# macu_board.net
KiCad netlist of a schematic drawn in EAGLE
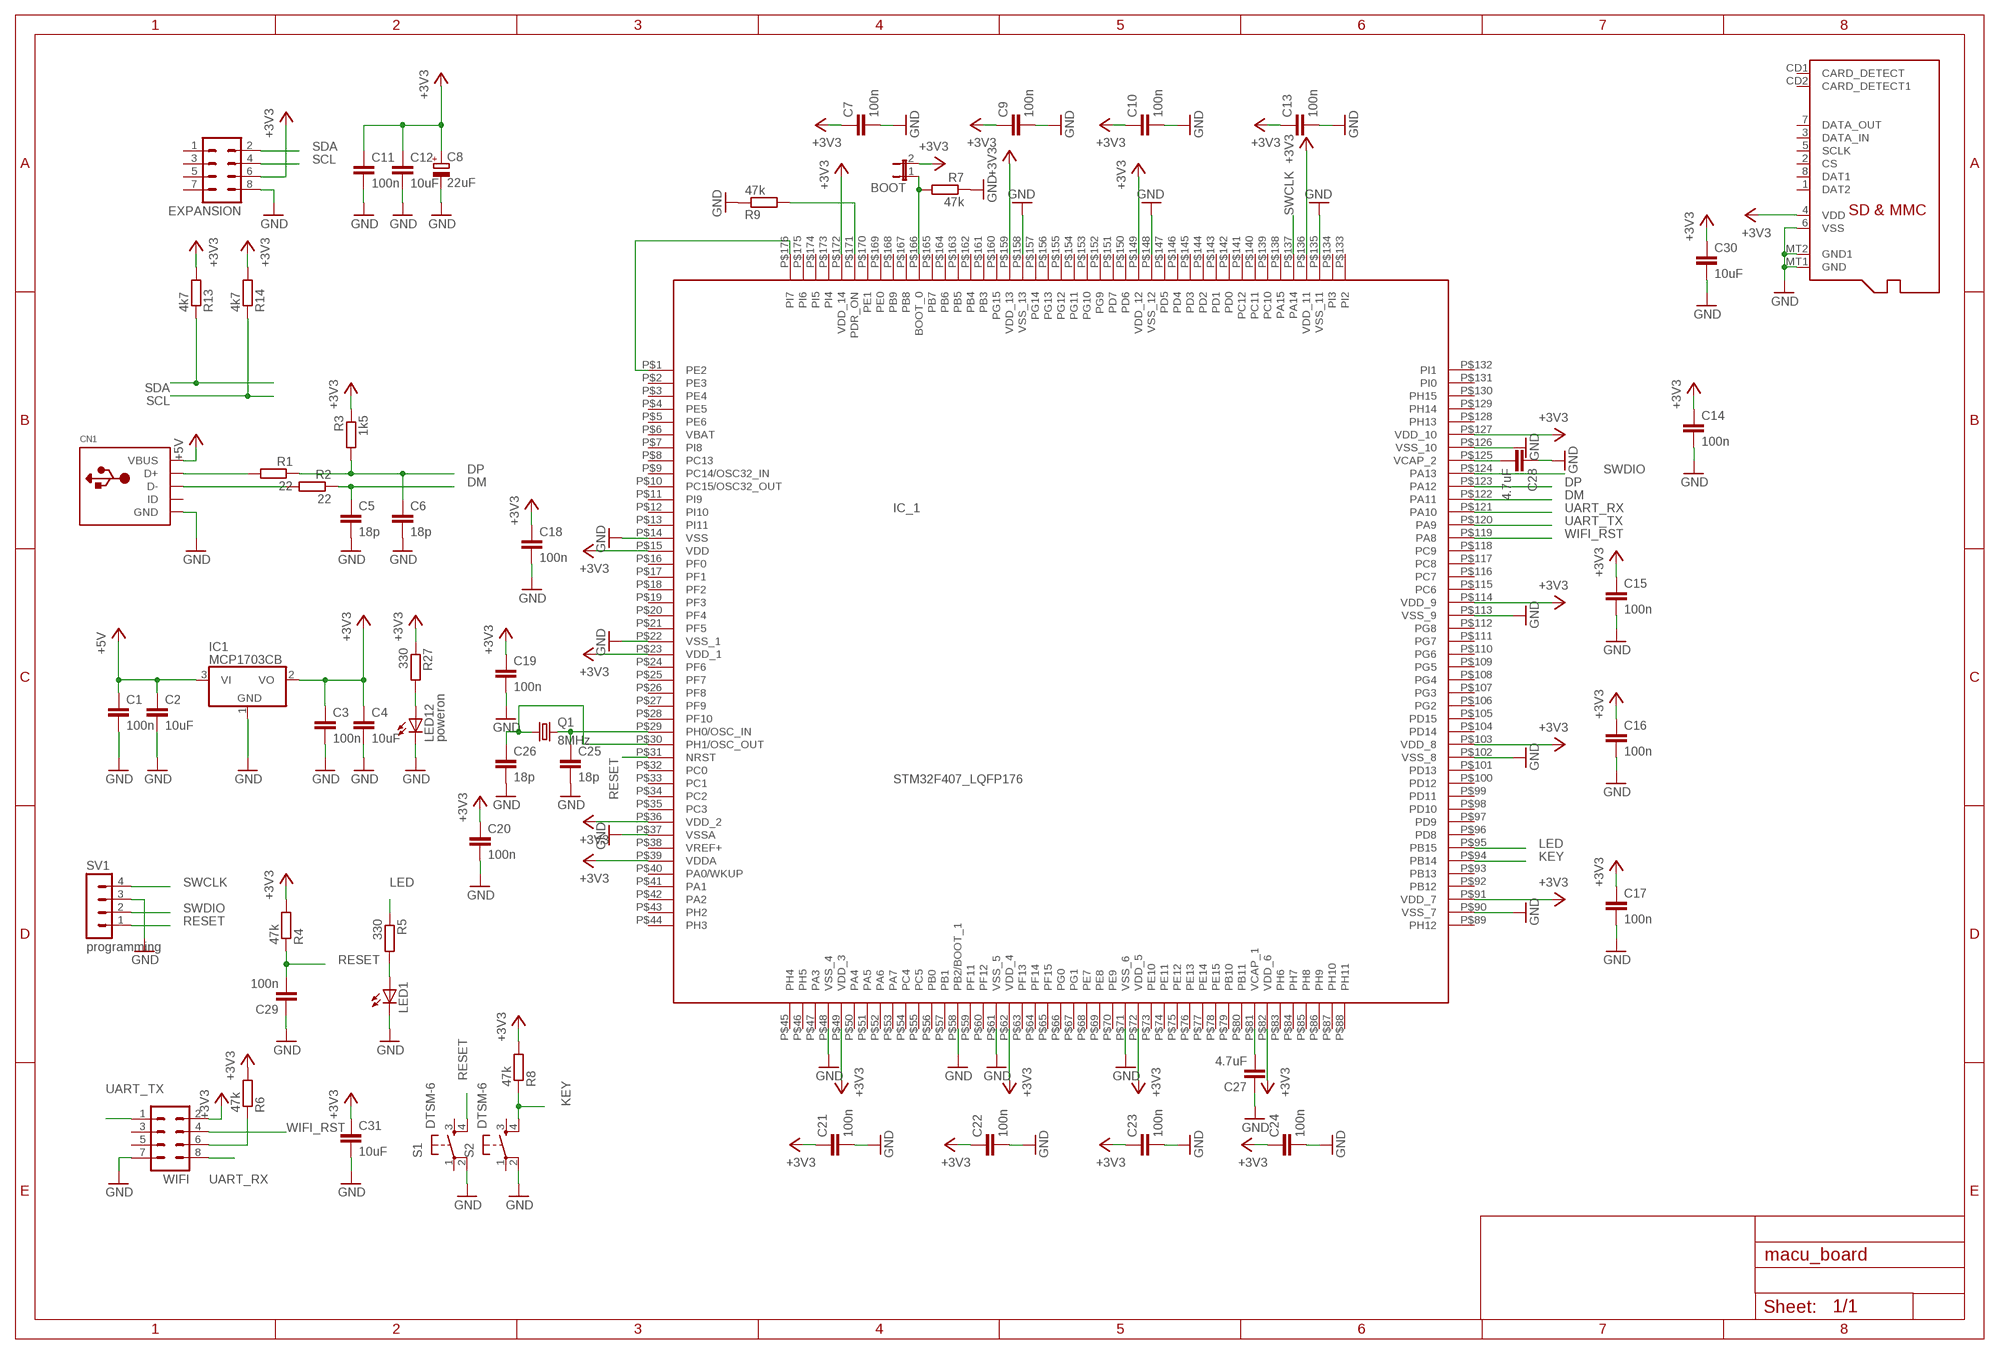
[diagram p0: schematic, sheet 1]

(export (version "E")
  (design (tool "Eeschema 10.0.6"))
  (components
    (comp (ref "BOOT")
      (value "JP1E")
      (footprint "eagle-import:JP1")
      (libsource (lib "eagle-import") (part "JP1E"))
    )
    (comp (ref "C1")
      (value "100n")
      (footprint "eagle-import:C0805")
      (libsource (lib "eagle-import") (part "C-EUC0805"))
    )
    (comp (ref "C2")
      (value "10uF")
      (footprint "eagle-import:C0805")
      (libsource (lib "eagle-import") (part "C-EUC0805"))
    )
    (comp (ref "C3")
      (value "100n")
      (footprint "eagle-import:C0805")
      (libsource (lib "eagle-import") (part "C-EUC0805"))
    )
    (comp (ref "C4")
      (value "10uF")
      (footprint "eagle-import:C0805")
      (libsource (lib "eagle-import") (part "C-EUC0805"))
    )
    (comp (ref "C5")
      (value "18p")
      (footprint "eagle-import:C0805")
      (libsource (lib "eagle-import") (part "C-EUC0805"))
    )
    (comp (ref "C6")
      (value "18p")
      (footprint "eagle-import:C0805")
      (libsource (lib "eagle-import") (part "C-EUC0805"))
    )
    (comp (ref "C7")
      (value "100n")
      (footprint "eagle-import:C0805")
      (libsource (lib "eagle-import") (part "C-EUC0805"))
    )
    (comp (ref "C8")
      (value "22uF")
      (footprint "eagle-import:153CLV-0505")
      (libsource (lib "eagle-import") (part "CPOL-EU153CLV-0505"))
    )
    (comp (ref "C9")
      (value "100n")
      (footprint "eagle-import:C0805")
      (libsource (lib "eagle-import") (part "C-EUC0805"))
    )
    (comp (ref "C10")
      (value "100n")
      (footprint "eagle-import:C0805")
      (libsource (lib "eagle-import") (part "C-EUC0805"))
    )
    (comp (ref "C11")
      (value "100n")
      (footprint "eagle-import:C0805")
      (libsource (lib "eagle-import") (part "C-EUC0805"))
    )
    (comp (ref "C12")
      (value "10uF")
      (footprint "eagle-import:C0805")
      (libsource (lib "eagle-import") (part "C-EUC0805"))
    )
    (comp (ref "C13")
      (value "100n")
      (footprint "eagle-import:C0805")
      (libsource (lib "eagle-import") (part "C-EUC0805"))
    )
    (comp (ref "C14")
      (value "100n")
      (footprint "eagle-import:C0805")
      (libsource (lib "eagle-import") (part "C-EUC0805"))
    )
    (comp (ref "C15")
      (value "100n")
      (footprint "eagle-import:C0805")
      (libsource (lib "eagle-import") (part "C-EUC0805"))
    )
    (comp (ref "C16")
      (value "100n")
      (footprint "eagle-import:C0805")
      (libsource (lib "eagle-import") (part "C-EUC0805"))
    )
    (comp (ref "C17")
      (value "100n")
      (footprint "eagle-import:C0805")
      (libsource (lib "eagle-import") (part "C-EUC0805"))
    )
    (comp (ref "C18")
      (value "100n")
      (footprint "eagle-import:C0805")
      (libsource (lib "eagle-import") (part "C-EUC0805"))
    )
    (comp (ref "C19")
      (value "100n")
      (footprint "eagle-import:C0805")
      (libsource (lib "eagle-import") (part "C-EUC0805"))
    )
    (comp (ref "C20")
      (value "100n")
      (footprint "eagle-import:C0805")
      (libsource (lib "eagle-import") (part "C-EUC0805"))
    )
    (comp (ref "C21")
      (value "100n")
      (footprint "eagle-import:C0805")
      (libsource (lib "eagle-import") (part "C-EUC0805"))
    )
    (comp (ref "C22")
      (value "100n")
      (footprint "eagle-import:C0805")
      (libsource (lib "eagle-import") (part "C-EUC0805"))
    )
    (comp (ref "C23")
      (value "100n")
      (footprint "eagle-import:C0805")
      (libsource (lib "eagle-import") (part "C-EUC0805"))
    )
    (comp (ref "C24")
      (value "100n")
      (footprint "eagle-import:C0805")
      (libsource (lib "eagle-import") (part "C-EUC0805"))
    )
    (comp (ref "C25")
      (value "18p")
      (footprint "eagle-import:C0805")
      (libsource (lib "eagle-import") (part "C-EUC0805"))
    )
    (comp (ref "C26")
      (value "18p")
      (footprint "eagle-import:C0805")
      (libsource (lib "eagle-import") (part "C-EUC0805"))
    )
    (comp (ref "C27")
      (value "4.7uF")
      (footprint "eagle-import:C0805")
      (libsource (lib "eagle-import") (part "C-EUC0805"))
    )
    (comp (ref "C28")
      (value "4.7uF")
      (footprint "eagle-import:C0805")
      (libsource (lib "eagle-import") (part "C-EUC0805"))
    )
    (comp (ref "C29")
      (value "100n")
      (footprint "eagle-import:C0805")
      (libsource (lib "eagle-import") (part "C-EUC0805"))
    )
    (comp (ref "C30")
      (value "10uF")
      (footprint "eagle-import:C0805")
      (libsource (lib "eagle-import") (part "C-EUC0805"))
    )
    (comp (ref "C31")
      (value "10uF")
      (footprint "eagle-import:C0805")
      (libsource (lib "eagle-import") (part "C-EUC0805"))
    )
    (comp (ref "CN1")
      (value "USBMINIB")
      (footprint "eagle-import:USB-MINIB")
      (libsource (lib "eagle-import") (part "USBMINIB"))
    )
    (comp (ref "EXPANSION")
      (value "MA04-2")
      (footprint "eagle-import:MA04-2")
      (libsource (lib "eagle-import") (part "MA04-2"))
    )
    (comp (ref "IC1")
      (value "MCP1703CB")
      (footprint "eagle-import:SOT23")
      (libsource (lib "eagle-import") (part "MCP1703CB"))
    )
    (comp (ref "IC_1")
      (value "STM32F407_LQFP176")
      (footprint "eagle-import:STM32F407_LQFP176")
      (libsource (lib "eagle-import") (part "STM32F407_LQFP176"))
    )
    (comp (ref "LED1")
      (value "LEDCHIPLED_1206")
      (footprint "eagle-import:CHIPLED_1206")
      (libsource (lib "eagle-import") (part "LEDCHIPLED_1206"))
    )
    (comp (ref "LED12")
      (value "poweron")
      (footprint "eagle-import:CHIPLED_1206")
      (libsource (lib "eagle-import") (part "LEDCHIPLED_1206"))
    )
    (comp (ref "Q1")
      (value "8MHz")
      (footprint "eagle-import:CTS406")
      (libsource (lib "eagle-import") (part "CRYSTALCTS406"))
    )
    (comp (ref "R1")
      (value "22")
      (footprint "eagle-import:M0805")
      (libsource (lib "eagle-import") (part "R-EU_M0805"))
    )
    (comp (ref "R2")
      (value "22")
      (footprint "eagle-import:M0805")
      (libsource (lib "eagle-import") (part "R-EU_M0805"))
    )
    (comp (ref "R3")
      (value "1k5")
      (footprint "eagle-import:M0805")
      (libsource (lib "eagle-import") (part "R-EU_M0805"))
    )
    (comp (ref "R4")
      (value "47k")
      (footprint "eagle-import:M0805")
      (libsource (lib "eagle-import") (part "R-EU_M0805"))
    )
    (comp (ref "R5")
      (value "330")
      (footprint "eagle-import:M0805")
      (libsource (lib "eagle-import") (part "R-EU_M0805"))
    )
    (comp (ref "R6")
      (value "47k")
      (footprint "eagle-import:M0805")
      (libsource (lib "eagle-import") (part "R-EU_M0805"))
    )
    (comp (ref "R7")
      (value "47k")
      (footprint "eagle-import:M0805")
      (libsource (lib "eagle-import") (part "R-EU_M0805"))
    )
    (comp (ref "R8")
      (value "47k")
      (footprint "eagle-import:M0805")
      (libsource (lib "eagle-import") (part "R-EU_M0805"))
    )
    (comp (ref "R9")
      (value "47k")
      (footprint "eagle-import:M0805")
      (libsource (lib "eagle-import") (part "R-EU_M0805"))
    )
    (comp (ref "R13")
      (value "4k7")
      (footprint "eagle-import:M0805")
      (libsource (lib "eagle-import") (part "R-EU_M0805"))
    )
    (comp (ref "R14")
      (value "4k7")
      (footprint "eagle-import:M0805")
      (libsource (lib "eagle-import") (part "R-EU_M0805"))
    )
    (comp (ref "R27")
      (value "330")
      (footprint "eagle-import:M0805")
      (libsource (lib "eagle-import") (part "R-EU_M0805"))
    )
    (comp (ref "S1")
      (value "DTSM-6")
      (footprint "eagle-import:DTSM-6")
      (libsource (lib "eagle-import") (part "DTSM-6"))
    )
    (comp (ref "S2")
      (value "DTSM-6")
      (footprint "eagle-import:DTSM-6")
      (libsource (lib "eagle-import") (part "DTSM-6"))
    )
    (comp (ref "SV1")
      (value "programming")
      (footprint "eagle-import:MA04-1")
      (libsource (lib "eagle-import") (part "MA04-1"))
    )
    (comp (ref "U$1")
      (value "MICROSD")
      (footprint "eagle-import:MICROSD")
      (libsource (lib "eagle-import") (part "MICROSD"))
    )
    (comp (ref "WIFI")
      (value "MA04-2")
      (footprint "eagle-import:MA04-2")
      (libsource (lib "eagle-import") (part "MA04-2"))
    )
  )
  (nets
    (net (code "1") (name "+3V3") (class "Default")
      (node (ref "BOOT") (pin "2") (pinfunction "2_2") (pintype "passive"))
      (node (ref "C10") (pin "1") (pinfunction "1_1") (pintype "passive"))
      (node (ref "C11") (pin "1") (pinfunction "1_1") (pintype "passive"))
      (node (ref "C12") (pin "1") (pinfunction "1_1") (pintype "passive"))
      (node (ref "C13") (pin "1") (pinfunction "1_1") (pintype "passive"))
      (node (ref "C14") (pin "1") (pinfunction "1_1") (pintype "passive"))
      (node (ref "C15") (pin "1") (pinfunction "1_1") (pintype "passive"))
      (node (ref "C16") (pin "1") (pinfunction "1_1") (pintype "passive"))
      (node (ref "C17") (pin "1") (pinfunction "1_1") (pintype "passive"))
      (node (ref "C18") (pin "1") (pinfunction "1_1") (pintype "passive"))
      (node (ref "C19") (pin "1") (pinfunction "1_1") (pintype "passive"))
      (node (ref "C20") (pin "1") (pinfunction "1_1") (pintype "passive"))
      (node (ref "C21") (pin "1") (pinfunction "1_1") (pintype "passive"))
      (node (ref "C22") (pin "1") (pinfunction "1_1") (pintype "passive"))
      (node (ref "C23") (pin "1") (pinfunction "1_1") (pintype "passive"))
      (node (ref "C24") (pin "1") (pinfunction "1_1") (pintype "passive"))
      (node (ref "C3") (pin "1") (pinfunction "1_1") (pintype "passive"))
      (node (ref "C30") (pin "1") (pinfunction "1_1") (pintype "passive"))
      (node (ref "C31") (pin "1") (pinfunction "1_1") (pintype "passive"))
      (node (ref "C4") (pin "1") (pinfunction "1_1") (pintype "passive"))
      (node (ref "C7") (pin "1") (pinfunction "1_1") (pintype "passive"))
      (node (ref "C8") (pin "+") (pinfunction "+_+") (pintype "passive"))
      (node (ref "C9") (pin "1") (pinfunction "1_1") (pintype "passive"))
      (node (ref "EXPANSION") (pin "6") (pinfunction "6_6") (pintype "passive"))
      (node (ref "IC1") (pin "2") (pinfunction "VO_2") (pintype "passive"))
      (node (ref "IC_1") (pin "P$103") (pinfunction "VDD_8_P$103") (pintype "power_in"))
      (node (ref "IC_1") (pin "P$114") (pinfunction "VDD_9_P$114") (pintype "power_in"))
      (node (ref "IC_1") (pin "P$127") (pinfunction "VDD_10_P$127") (pintype "power_in"))
      (node (ref "IC_1") (pin "P$136") (pinfunction "VDD_11_P$136") (pintype "power_in"))
      (node (ref "IC_1") (pin "P$149") (pinfunction "VDD_12_P$149") (pintype "power_in"))
      (node (ref "IC_1") (pin "P$15") (pinfunction "VDD_P$15") (pintype "power_in"))
      (node (ref "IC_1") (pin "P$159") (pinfunction "VDD_13_P$159") (pintype "power_in"))
      (node (ref "IC_1") (pin "P$172") (pinfunction "VDD_14_P$172") (pintype "power_in"))
      (node (ref "IC_1") (pin "P$23") (pinfunction "VDD_1_P$23") (pintype "power_in"))
      (node (ref "IC_1") (pin "P$36") (pinfunction "VDD_2_P$36") (pintype "power_in"))
      (node (ref "IC_1") (pin "P$39") (pinfunction "VDDA_P$39") (pintype "power_in"))
      (node (ref "IC_1") (pin "P$49") (pinfunction "VDD_3_P$49") (pintype "power_in"))
      (node (ref "IC_1") (pin "P$62") (pinfunction "VDD_4_P$62") (pintype "power_in"))
      (node (ref "IC_1") (pin "P$72") (pinfunction "VDD_5_P$72") (pintype "power_in"))
      (node (ref "IC_1") (pin "P$82") (pinfunction "VDD_6_P$82") (pintype "power_in"))
      (node (ref "IC_1") (pin "P$91") (pinfunction "VDD_7_P$91") (pintype "power_in"))
      (node (ref "R13") (pin "2") (pinfunction "2_2") (pintype "passive"))
      (node (ref "R14") (pin "2") (pinfunction "2_2") (pintype "passive"))
      (node (ref "R27") (pin "1") (pinfunction "1_1") (pintype "passive"))
      (node (ref "R3") (pin "1") (pinfunction "1_1") (pintype "passive"))
      (node (ref "R4") (pin "2") (pinfunction "2_2") (pintype "passive"))
      (node (ref "R6") (pin "2") (pinfunction "2_2") (pintype "passive"))
      (node (ref "R8") (pin "2") (pinfunction "2_2") (pintype "passive"))
      (node (ref "U$1") (pin "4") (pinfunction "VDD_4") (pintype "power_in"))
      (node (ref "WIFI") (pin "2") (pinfunction "2_2") (pintype "passive"))
    )
    (net (code "2") (name "+5V") (class "Default")
      (node (ref "C1") (pin "1") (pinfunction "1_1") (pintype "passive"))
      (node (ref "C2") (pin "1") (pinfunction "1_1") (pintype "passive"))
      (node (ref "CN1") (pin "VBUS") (pinfunction "VBUS_VBUS") (pintype "power_in"))
      (node (ref "IC1") (pin "3") (pinfunction "VI_3") (pintype "input"))
    )
    (net (code "3") (name "/DM") (class "Default")
      (node (ref "C5") (pin "1") (pinfunction "1_1") (pintype "passive"))
      (node (ref "IC_1") (pin "P$122") (pinfunction "PA11_P$122") (pintype "bidirectional"))
      (node (ref "R2") (pin "1") (pinfunction "1_1") (pintype "passive"))
    )
    (net (code "4") (name "/DP") (class "Default")
      (node (ref "C6") (pin "1") (pinfunction "1_1") (pintype "passive"))
      (node (ref "IC_1") (pin "P$123") (pinfunction "PA12_P$123") (pintype "bidirectional"))
      (node (ref "R1") (pin "1") (pinfunction "1_1") (pintype "passive"))
      (node (ref "R3") (pin "2") (pinfunction "2_2") (pintype "passive"))
    )
    (net (code "5") (name "/KEY") (class "Default")
      (node (ref "IC_1") (pin "P$94") (pinfunction "PB14_P$94") (pintype "bidirectional"))
      (node (ref "R8") (pin "1") (pinfunction "1_1") (pintype "passive"))
      (node (ref "S2") (pin "4") (pinfunction "4_4") (pintype "passive"))
    )
    (net (code "6") (name "/LED") (class "Default")
      (node (ref "IC_1") (pin "P$95") (pinfunction "PB15_P$95") (pintype "bidirectional"))
      (node (ref "R5") (pin "1") (pinfunction "1_1") (pintype "passive"))
    )
    (net (code "7") (name "/RESET") (class "Default")
      (node (ref "C29") (pin "2") (pinfunction "2_2") (pintype "passive"))
      (node (ref "IC_1") (pin "P$31") (pinfunction "NRST_P$31") (pintype "bidirectional"))
      (node (ref "R4") (pin "1") (pinfunction "1_1") (pintype "passive"))
      (node (ref "S1") (pin "4") (pinfunction "4_4") (pintype "passive"))
      (node (ref "SV1") (pin "1") (pinfunction "1_1") (pintype "passive"))
    )
    (net (code "8") (name "/SCL") (class "Default")
      (node (ref "EXPANSION") (pin "4") (pinfunction "4_4") (pintype "passive"))
      (node (ref "R14") (pin "1") (pinfunction "1_1") (pintype "passive"))
    )
    (net (code "9") (name "/SDA") (class "Default")
      (node (ref "EXPANSION") (pin "2") (pinfunction "2_2") (pintype "passive"))
      (node (ref "R13") (pin "1") (pinfunction "1_1") (pintype "passive"))
    )
    (net (code "10") (name "/SWCLK") (class "Default")
      (node (ref "IC_1") (pin "P$137") (pinfunction "PA14_P$137") (pintype "bidirectional"))
      (node (ref "SV1") (pin "4") (pinfunction "4_4") (pintype "passive"))
    )
    (net (code "11") (name "/SWDIO") (class "Default")
      (node (ref "IC_1") (pin "P$124") (pinfunction "PA13_P$124") (pintype "bidirectional"))
      (node (ref "SV1") (pin "2") (pinfunction "2_2") (pintype "passive"))
    )
    (net (code "12") (name "/UART_RX") (class "Default")
      (node (ref "IC_1") (pin "P$121") (pinfunction "PA10_P$121") (pintype "bidirectional"))
      (node (ref "WIFI") (pin "8") (pinfunction "8_8") (pintype "passive"))
    )
    (net (code "13") (name "/UART_TX") (class "Default")
      (node (ref "IC_1") (pin "P$120") (pinfunction "PA9_P$120") (pintype "bidirectional"))
      (node (ref "WIFI") (pin "1") (pinfunction "1_1") (pintype "passive"))
    )
    (net (code "14") (name "/VBAT") (class "Default")
      (node (ref "IC_1") (pin "P$6") (pinfunction "VBAT_P$6") (pintype "power_in"))
    )
    (net (code "15") (name "/VREF+") (class "Default")
      (node (ref "IC_1") (pin "P$38") (pinfunction "VREF+_P$38") (pintype "power_in"))
    )
    (net (code "16") (name "/WIFI_RST") (class "Default")
      (node (ref "IC_1") (pin "P$119") (pinfunction "PA8_P$119") (pintype "bidirectional"))
      (node (ref "WIFI") (pin "4") (pinfunction "4_4") (pintype "passive"))
    )
    (net (code "17") (name "GND") (class "Default")
      (node (ref "C1") (pin "2") (pinfunction "2_2") (pintype "passive"))
      (node (ref "C10") (pin "2") (pinfunction "2_2") (pintype "passive"))
      (node (ref "C11") (pin "2") (pinfunction "2_2") (pintype "passive"))
      (node (ref "C12") (pin "2") (pinfunction "2_2") (pintype "passive"))
      (node (ref "C13") (pin "2") (pinfunction "2_2") (pintype "passive"))
      (node (ref "C14") (pin "2") (pinfunction "2_2") (pintype "passive"))
      (node (ref "C15") (pin "2") (pinfunction "2_2") (pintype "passive"))
      (node (ref "C16") (pin "2") (pinfunction "2_2") (pintype "passive"))
      (node (ref "C17") (pin "2") (pinfunction "2_2") (pintype "passive"))
      (node (ref "C18") (pin "2") (pinfunction "2_2") (pintype "passive"))
      (node (ref "C19") (pin "2") (pinfunction "2_2") (pintype "passive"))
      (node (ref "C2") (pin "2") (pinfunction "2_2") (pintype "passive"))
      (node (ref "C20") (pin "2") (pinfunction "2_2") (pintype "passive"))
      (node (ref "C21") (pin "2") (pinfunction "2_2") (pintype "passive"))
      (node (ref "C22") (pin "2") (pinfunction "2_2") (pintype "passive"))
      (node (ref "C23") (pin "2") (pinfunction "2_2") (pintype "passive"))
      (node (ref "C24") (pin "2") (pinfunction "2_2") (pintype "passive"))
      (node (ref "C25") (pin "2") (pinfunction "2_2") (pintype "passive"))
      (node (ref "C26") (pin "2") (pinfunction "2_2") (pintype "passive"))
      (node (ref "C27") (pin "1") (pinfunction "1_1") (pintype "passive"))
      (node (ref "C28") (pin "1") (pinfunction "1_1") (pintype "passive"))
      (node (ref "C29") (pin "1") (pinfunction "1_1") (pintype "passive"))
      (node (ref "C3") (pin "2") (pinfunction "2_2") (pintype "passive"))
      (node (ref "C30") (pin "2") (pinfunction "2_2") (pintype "passive"))
      (node (ref "C31") (pin "2") (pinfunction "2_2") (pintype "passive"))
      (node (ref "C4") (pin "2") (pinfunction "2_2") (pintype "passive"))
      (node (ref "C5") (pin "2") (pinfunction "2_2") (pintype "passive"))
      (node (ref "C6") (pin "2") (pinfunction "2_2") (pintype "passive"))
      (node (ref "C7") (pin "2") (pinfunction "2_2") (pintype "passive"))
      (node (ref "C8") (pin "-") (pinfunction "-_-") (pintype "passive"))
      (node (ref "C9") (pin "2") (pinfunction "2_2") (pintype "passive"))
      (node (ref "CN1") (pin "GND") (pinfunction "GND_GND") (pintype "power_in"))
      (node (ref "EXPANSION") (pin "8") (pinfunction "8_8") (pintype "passive"))
      (node (ref "IC1") (pin "1") (pinfunction "GND_1") (pintype "passive"))
      (node (ref "IC_1") (pin "P$102") (pinfunction "VSS_8_P$102") (pintype "power_in"))
      (node (ref "IC_1") (pin "P$113") (pinfunction "VSS_9_P$113") (pintype "power_in"))
      (node (ref "IC_1") (pin "P$126") (pinfunction "VSS_10_P$126") (pintype "power_in"))
      (node (ref "IC_1") (pin "P$135") (pinfunction "VSS_11_P$135") (pintype "power_in"))
      (node (ref "IC_1") (pin "P$14") (pinfunction "VSS_P$14") (pintype "power_in"))
      (node (ref "IC_1") (pin "P$148") (pinfunction "VSS_12_P$148") (pintype "power_in"))
      (node (ref "IC_1") (pin "P$158") (pinfunction "VSS_13_P$158") (pintype "power_in"))
      (node (ref "IC_1") (pin "P$22") (pinfunction "VSS_1_P$22") (pintype "power_in"))
      (node (ref "IC_1") (pin "P$37") (pinfunction "VSSA_P$37") (pintype "power_in"))
      (node (ref "IC_1") (pin "P$48") (pinfunction "VSS_4_P$48") (pintype "power_in"))
      (node (ref "IC_1") (pin "P$58") (pinfunction "PB2/BOOT_1_P$58") (pintype "bidirectional"))
      (node (ref "IC_1") (pin "P$61") (pinfunction "VSS_5_P$61") (pintype "power_in"))
      (node (ref "IC_1") (pin "P$71") (pinfunction "VSS_6_P$71") (pintype "power_in"))
      (node (ref "IC_1") (pin "P$90") (pinfunction "VSS_7_P$90") (pintype "power_in"))
      (node (ref "LED1") (pin "C") (pinfunction "C_C") (pintype "passive"))
      (node (ref "LED12") (pin "C") (pinfunction "C_C") (pintype "passive"))
      (node (ref "R7") (pin "1") (pinfunction "1_1") (pintype "passive"))
      (node (ref "R9") (pin "1") (pinfunction "1_1") (pintype "passive"))
      (node (ref "S1") (pin "2") (pinfunction "2_2") (pintype "passive"))
      (node (ref "S2") (pin "2") (pinfunction "2_2") (pintype "passive"))
      (node (ref "SV1") (pin "3") (pinfunction "3_3") (pintype "passive"))
      (node (ref "U$1") (pin "6") (pinfunction "VSS_6") (pintype "power_in"))
      (node (ref "U$1") (pin "MT1") (pinfunction "GND_MT1") (pintype "power_in"))
      (node (ref "U$1") (pin "MT2") (pinfunction "GND1_MT2") (pintype "power_in"))
      (node (ref "WIFI") (pin "7") (pinfunction "7_7") (pintype "passive"))
    )
    (net (code "18") (name "Net-(CN1-PadD+)") (class "Default")
      (node (ref "CN1") (pin "D+") (pinfunction "D+_D+") (pintype "bidirectional"))
      (node (ref "R1") (pin "2") (pinfunction "2_2") (pintype "passive"))
    )
    (net (code "19") (name "Net-(CN1-PadD-)") (class "Default")
      (node (ref "CN1") (pin "D-") (pinfunction "D-_D-") (pintype "bidirectional"))
      (node (ref "R2") (pin "2") (pinfunction "2_2") (pintype "passive"))
    )
    (net (code "20") (name "Net-(IC_1-BOOT_0)") (class "Default")
      (node (ref "BOOT") (pin "1") (pinfunction "1_1") (pintype "passive"))
      (node (ref "IC_1") (pin "P$166") (pinfunction "BOOT_0_P$166") (pintype "bidirectional"))
      (node (ref "R7") (pin "2") (pinfunction "2_2") (pintype "passive"))
    )
    (net (code "21") (name "Net-(IC_1-PDR_ON)") (class "Default")
      (node (ref "IC_1") (pin "P$171") (pinfunction "PDR_ON_P$171") (pintype "bidirectional"))
      (node (ref "R9") (pin "2") (pinfunction "2_2") (pintype "passive"))
    )
    (net (code "22") (name "Net-(IC_1-PE2)") (class "Default")
      (node (ref "IC_1") (pin "P$1") (pinfunction "PE2_P$1") (pintype "bidirectional"))
      (node (ref "IC_1") (pin "P$176") (pinfunction "PI7_P$176") (pintype "bidirectional"))
    )
    (net (code "23") (name "Net-(IC_1-PH0{slash}OSC_IN)") (class "Default")
      (node (ref "C25") (pin "1") (pinfunction "1_1") (pintype "passive"))
      (node (ref "IC_1") (pin "P$29") (pinfunction "PH0/OSC_IN_P$29") (pintype "bidirectional"))
      (node (ref "Q1") (pin "3") (pinfunction "2_3") (pintype "passive"))
    )
    (net (code "24") (name "Net-(IC_1-PH1{slash}OSC_OUT)") (class "Default")
      (node (ref "C26") (pin "1") (pinfunction "1_1") (pintype "passive"))
      (node (ref "IC_1") (pin "P$30") (pinfunction "PH1/OSC_OUT_P$30") (pintype "bidirectional"))
      (node (ref "Q1") (pin "1") (pinfunction "1_1") (pintype "passive"))
    )
    (net (code "25") (name "Net-(IC_1-VCAP_1)") (class "Default")
      (node (ref "C27") (pin "2") (pinfunction "2_2") (pintype "passive"))
      (node (ref "IC_1") (pin "P$81") (pinfunction "VCAP_1_P$81") (pintype "power_in"))
    )
    (net (code "26") (name "Net-(IC_1-VCAP_2)") (class "Default")
      (node (ref "C28") (pin "2") (pinfunction "2_2") (pintype "passive"))
      (node (ref "IC_1") (pin "P$125") (pinfunction "VCAP_2_P$125") (pintype "power_in"))
    )
    (net (code "27") (name "Net-(LED1-PadA)") (class "Default")
      (node (ref "LED1") (pin "A") (pinfunction "A_A") (pintype "passive"))
      (node (ref "R5") (pin "2") (pinfunction "2_2") (pintype "passive"))
    )
    (net (code "28") (name "Net-(LED12-PadA)") (class "Default")
      (node (ref "LED12") (pin "A") (pinfunction "A_A") (pintype "passive"))
      (node (ref "R27") (pin "2") (pinfunction "2_2") (pintype "passive"))
    )
    (net (code "29") (name "Net-(R6-Pad1)") (class "Default")
      (node (ref "R6") (pin "1") (pinfunction "1_1") (pintype "passive"))
      (node (ref "WIFI") (pin "6") (pinfunction "6_6") (pintype "passive"))
    )
    (net (code "30") (name "unconnected-(CN1-PadID)") (class "Default")
      (node (ref "CN1") (pin "ID") (pinfunction "ID_ID") (pintype "bidirectional"))
    )
    (net (code "31") (name "unconnected-(EXPANSION-Pad1)") (class "Default")
      (node (ref "EXPANSION") (pin "1") (pinfunction "1_1") (pintype "passive"))
    )
    (net (code "32") (name "unconnected-(EXPANSION-Pad3)") (class "Default")
      (node (ref "EXPANSION") (pin "3") (pinfunction "3_3") (pintype "passive"))
    )
    (net (code "33") (name "unconnected-(EXPANSION-Pad5)") (class "Default")
      (node (ref "EXPANSION") (pin "5") (pinfunction "5_5") (pintype "passive"))
    )
    (net (code "34") (name "unconnected-(EXPANSION-Pad7)") (class "Default")
      (node (ref "EXPANSION") (pin "7") (pinfunction "7_7") (pintype "passive"))
    )
    (net (code "35") (name "unconnected-(IC_1-PA0{slash}WKUP-PadP$40)") (class "Default")
      (node (ref "IC_1") (pin "P$40") (pinfunction "PA0/WKUP_P$40") (pintype "bidirectional"))
    )
    (net (code "36") (name "unconnected-(IC_1-PA1-PadP$41)") (class "Default")
      (node (ref "IC_1") (pin "P$41") (pinfunction "PA1_P$41") (pintype "bidirectional"))
    )
    (net (code "37") (name "unconnected-(IC_1-PA2-PadP$42)") (class "Default")
      (node (ref "IC_1") (pin "P$42") (pinfunction "PA2_P$42") (pintype "bidirectional"))
    )
    (net (code "38") (name "unconnected-(IC_1-PA3-PadP$47)") (class "Default")
      (node (ref "IC_1") (pin "P$47") (pinfunction "PA3_P$47") (pintype "bidirectional"))
    )
    (net (code "39") (name "unconnected-(IC_1-PA4-PadP$50)") (class "Default")
      (node (ref "IC_1") (pin "P$50") (pinfunction "PA4_P$50") (pintype "bidirectional"))
    )
    (net (code "40") (name "unconnected-(IC_1-PA5-PadP$51)") (class "Default")
      (node (ref "IC_1") (pin "P$51") (pinfunction "PA5_P$51") (pintype "bidirectional"))
    )
    (net (code "41") (name "unconnected-(IC_1-PA6-PadP$52)") (class "Default")
      (node (ref "IC_1") (pin "P$52") (pinfunction "PA6_P$52") (pintype "bidirectional"))
    )
    (net (code "42") (name "unconnected-(IC_1-PA7-PadP$53)") (class "Default")
      (node (ref "IC_1") (pin "P$53") (pinfunction "PA7_P$53") (pintype "bidirectional"))
    )
    (net (code "43") (name "unconnected-(IC_1-PA15-PadP$138)") (class "Default")
      (node (ref "IC_1") (pin "P$138") (pinfunction "PA15_P$138") (pintype "bidirectional"))
    )
    (net (code "44") (name "unconnected-(IC_1-PB0-PadP$56)") (class "Default")
      (node (ref "IC_1") (pin "P$56") (pinfunction "PB0_P$56") (pintype "bidirectional"))
    )
    (net (code "45") (name "unconnected-(IC_1-PB1-PadP$57)") (class "Default")
      (node (ref "IC_1") (pin "P$57") (pinfunction "PB1_P$57") (pintype "bidirectional"))
    )
    (net (code "46") (name "unconnected-(IC_1-PB3-PadP$161)") (class "Default")
      (node (ref "IC_1") (pin "P$161") (pinfunction "PB3_P$161") (pintype "bidirectional"))
    )
    (net (code "47") (name "unconnected-(IC_1-PB4-PadP$162)") (class "Default")
      (node (ref "IC_1") (pin "P$162") (pinfunction "PB4_P$162") (pintype "bidirectional"))
    )
    (net (code "48") (name "unconnected-(IC_1-PB5-PadP$163)") (class "Default")
      (node (ref "IC_1") (pin "P$163") (pinfunction "PB5_P$163") (pintype "bidirectional"))
    )
    (net (code "49") (name "unconnected-(IC_1-PB6-PadP$164)") (class "Default")
      (node (ref "IC_1") (pin "P$164") (pinfunction "PB6_P$164") (pintype "bidirectional"))
    )
    (net (code "50") (name "unconnected-(IC_1-PB7-PadP$165)") (class "Default")
      (node (ref "IC_1") (pin "P$165") (pinfunction "PB7_P$165") (pintype "bidirectional"))
    )
    (net (code "51") (name "unconnected-(IC_1-PB8-PadP$167)") (class "Default")
      (node (ref "IC_1") (pin "P$167") (pinfunction "PB8_P$167") (pintype "bidirectional"))
    )
    (net (code "52") (name "unconnected-(IC_1-PB9-PadP$168)") (class "Default")
      (node (ref "IC_1") (pin "P$168") (pinfunction "PB9_P$168") (pintype "bidirectional"))
    )
    (net (code "53") (name "unconnected-(IC_1-PB10-PadP$79)") (class "Default")
      (node (ref "IC_1") (pin "P$79") (pinfunction "PB10_P$79") (pintype "bidirectional"))
    )
    (net (code "54") (name "unconnected-(IC_1-PB11-PadP$80)") (class "Default")
      (node (ref "IC_1") (pin "P$80") (pinfunction "PB11_P$80") (pintype "bidirectional"))
    )
    (net (code "55") (name "unconnected-(IC_1-PB12-PadP$92)") (class "Default")
      (node (ref "IC_1") (pin "P$92") (pinfunction "PB12_P$92") (pintype "bidirectional"))
    )
    (net (code "56") (name "unconnected-(IC_1-PB13-PadP$93)") (class "Default")
      (node (ref "IC_1") (pin "P$93") (pinfunction "PB13_P$93") (pintype "bidirectional"))
    )
    (net (code "57") (name "unconnected-(IC_1-PC0-PadP$32)") (class "Default")
      (node (ref "IC_1") (pin "P$32") (pinfunction "PC0_P$32") (pintype "bidirectional"))
    )
    (net (code "58") (name "unconnected-(IC_1-PC1-PadP$33)") (class "Default")
      (node (ref "IC_1") (pin "P$33") (pinfunction "PC1_P$33") (pintype "bidirectional"))
    )
    (net (code "59") (name "unconnected-(IC_1-PC2-PadP$34)") (class "Default")
      (node (ref "IC_1") (pin "P$34") (pinfunction "PC2_P$34") (pintype "bidirectional"))
    )
    (net (code "60") (name "unconnected-(IC_1-PC3-PadP$35)") (class "Default")
      (node (ref "IC_1") (pin "P$35") (pinfunction "PC3_P$35") (pintype "bidirectional"))
    )
    (net (code "61") (name "unconnected-(IC_1-PC4-PadP$54)") (class "Default")
      (node (ref "IC_1") (pin "P$54") (pinfunction "PC4_P$54") (pintype "bidirectional"))
    )
    (net (code "62") (name "unconnected-(IC_1-PC5-PadP$55)") (class "Default")
      (node (ref "IC_1") (pin "P$55") (pinfunction "PC5_P$55") (pintype "bidirectional"))
    )
    (net (code "63") (name "unconnected-(IC_1-PC6-PadP$115)") (class "Default")
      (node (ref "IC_1") (pin "P$115") (pinfunction "PC6_P$115") (pintype "bidirectional"))
    )
    (net (code "64") (name "unconnected-(IC_1-PC7-PadP$116)") (class "Default")
      (node (ref "IC_1") (pin "P$116") (pinfunction "PC7_P$116") (pintype "bidirectional"))
    )
    (net (code "65") (name "unconnected-(IC_1-PC8-PadP$117)") (class "Default")
      (node (ref "IC_1") (pin "P$117") (pinfunction "PC8_P$117") (pintype "bidirectional"))
    )
    (net (code "66") (name "unconnected-(IC_1-PC9-PadP$118)") (class "Default")
      (node (ref "IC_1") (pin "P$118") (pinfunction "PC9_P$118") (pintype "bidirectional"))
    )
    (net (code "67") (name "unconnected-(IC_1-PC10-PadP$139)") (class "Default")
      (node (ref "IC_1") (pin "P$139") (pinfunction "PC10_P$139") (pintype "bidirectional"))
    )
    (net (code "68") (name "unconnected-(IC_1-PC11-PadP$140)") (class "Default")
      (node (ref "IC_1") (pin "P$140") (pinfunction "PC11_P$140") (pintype "bidirectional"))
    )
    (net (code "69") (name "unconnected-(IC_1-PC12-PadP$141)") (class "Default")
      (node (ref "IC_1") (pin "P$141") (pinfunction "PC12_P$141") (pintype "bidirectional"))
    )
    (net (code "70") (name "unconnected-(IC_1-PC13-PadP$8)") (class "Default")
      (node (ref "IC_1") (pin "P$8") (pinfunction "PC13_P$8") (pintype "bidirectional"))
    )
    (net (code "71") (name "unconnected-(IC_1-PC14{slash}OSC32_IN-PadP$9)") (class "Default")
      (node (ref "IC_1") (pin "P$9") (pinfunction "PC14/OSC32_IN_P$9") (pintype "bidirectional"))
    )
    (net (code "72") (name "unconnected-(IC_1-PC15{slash}OSC32_OUT-PadP$10)") (class "Default")
      (node (ref "IC_1") (pin "P$10") (pinfunction "PC15/OSC32_OUT_P$10") (pintype "bidirectional"))
    )
    (net (code "73") (name "unconnected-(IC_1-PD0-PadP$142)") (class "Default")
      (node (ref "IC_1") (pin "P$142") (pinfunction "PD0_P$142") (pintype "bidirectional"))
    )
    (net (code "74") (name "unconnected-(IC_1-PD1-PadP$143)") (class "Default")
      (node (ref "IC_1") (pin "P$143") (pinfunction "PD1_P$143") (pintype "bidirectional"))
    )
    (net (code "75") (name "unconnected-(IC_1-PD2-PadP$144)") (class "Default")
      (node (ref "IC_1") (pin "P$144") (pinfunction "PD2_P$144") (pintype "bidirectional"))
    )
    (net (code "76") (name "unconnected-(IC_1-PD3-PadP$145)") (class "Default")
      (node (ref "IC_1") (pin "P$145") (pinfunction "PD3_P$145") (pintype "bidirectional"))
    )
    (net (code "77") (name "unconnected-(IC_1-PD4-PadP$146)") (class "Default")
      (node (ref "IC_1") (pin "P$146") (pinfunction "PD4_P$146") (pintype "bidirectional"))
    )
    (net (code "78") (name "unconnected-(IC_1-PD5-PadP$147)") (class "Default")
      (node (ref "IC_1") (pin "P$147") (pinfunction "PD5_P$147") (pintype "bidirectional"))
    )
    (net (code "79") (name "unconnected-(IC_1-PD6-PadP$150)") (class "Default")
      (node (ref "IC_1") (pin "P$150") (pinfunction "PD6_P$150") (pintype "bidirectional"))
    )
    (net (code "80") (name "unconnected-(IC_1-PD7-PadP$151)") (class "Default")
      (node (ref "IC_1") (pin "P$151") (pinfunction "PD7_P$151") (pintype "bidirectional"))
    )
    (net (code "81") (name "unconnected-(IC_1-PD8-PadP$96)") (class "Default")
      (node (ref "IC_1") (pin "P$96") (pinfunction "PD8_P$96") (pintype "bidirectional"))
    )
    (net (code "82") (name "unconnected-(IC_1-PD9-PadP$97)") (class "Default")
      (node (ref "IC_1") (pin "P$97") (pinfunction "PD9_P$97") (pintype "bidirectional"))
    )
    (net (code "83") (name "unconnected-(IC_1-PD10-PadP$98)") (class "Default")
      (node (ref "IC_1") (pin "P$98") (pinfunction "PD10_P$98") (pintype "bidirectional"))
    )
    (net (code "84") (name "unconnected-(IC_1-PD11-PadP$99)") (class "Default")
      (node (ref "IC_1") (pin "P$99") (pinfunction "PD11_P$99") (pintype "bidirectional"))
    )
    (net (code "85") (name "unconnected-(IC_1-PD12-PadP$100)") (class "Default")
      (node (ref "IC_1") (pin "P$100") (pinfunction "PD12_P$100") (pintype "bidirectional"))
    )
    (net (code "86") (name "unconnected-(IC_1-PD13-PadP$101)") (class "Default")
      (node (ref "IC_1") (pin "P$101") (pinfunction "PD13_P$101") (pintype "bidirectional"))
    )
    (net (code "87") (name "unconnected-(IC_1-PD14-PadP$104)") (class "Default")
      (node (ref "IC_1") (pin "P$104") (pinfunction "PD14_P$104") (pintype "bidirectional"))
    )
    (net (code "88") (name "unconnected-(IC_1-PD15-PadP$105)") (class "Default")
      (node (ref "IC_1") (pin "P$105") (pinfunction "PD15_P$105") (pintype "bidirectional"))
    )
    (net (code "89") (name "unconnected-(IC_1-PE0-PadP$169)") (class "Default")
      (node (ref "IC_1") (pin "P$169") (pinfunction "PE0_P$169") (pintype "bidirectional"))
    )
    (net (code "90") (name "unconnected-(IC_1-PE1-PadP$170)") (class "Default")
      (node (ref "IC_1") (pin "P$170") (pinfunction "PE1_P$170") (pintype "bidirectional"))
    )
    (net (code "91") (name "unconnected-(IC_1-PE3-PadP$2)") (class "Default")
      (node (ref "IC_1") (pin "P$2") (pinfunction "PE3_P$2") (pintype "bidirectional"))
    )
    (net (code "92") (name "unconnected-(IC_1-PE4-PadP$3)") (class "Default")
      (node (ref "IC_1") (pin "P$3") (pinfunction "PE4_P$3") (pintype "bidirectional"))
    )
    (net (code "93") (name "unconnected-(IC_1-PE5-PadP$4)") (class "Default")
      (node (ref "IC_1") (pin "P$4") (pinfunction "PE5_P$4") (pintype "bidirectional"))
    )
    (net (code "94") (name "unconnected-(IC_1-PE6-PadP$5)") (class "Default")
      (node (ref "IC_1") (pin "P$5") (pinfunction "PE6_P$5") (pintype "bidirectional"))
    )
    (net (code "95") (name "unconnected-(IC_1-PE7-PadP$68)") (class "Default")
      (node (ref "IC_1") (pin "P$68") (pinfunction "PE7_P$68") (pintype "bidirectional"))
    )
    (net (code "96") (name "unconnected-(IC_1-PE8-PadP$69)") (class "Default")
      (node (ref "IC_1") (pin "P$69") (pinfunction "PE8_P$69") (pintype "bidirectional"))
    )
    (net (code "97") (name "unconnected-(IC_1-PE9-PadP$70)") (class "Default")
      (node (ref "IC_1") (pin "P$70") (pinfunction "PE9_P$70") (pintype "bidirectional"))
    )
    (net (code "98") (name "unconnected-(IC_1-PE10-PadP$73)") (class "Default")
      (node (ref "IC_1") (pin "P$73") (pinfunction "PE10_P$73") (pintype "bidirectional"))
    )
    (net (code "99") (name "unconnected-(IC_1-PE11-PadP$74)") (class "Default")
      (node (ref "IC_1") (pin "P$74") (pinfunction "PE11_P$74") (pintype "bidirectional"))
    )
    (net (code "100") (name "unconnected-(IC_1-PE12-PadP$75)") (class "Default")
      (node (ref "IC_1") (pin "P$75") (pinfunction "PE12_P$75") (pintype "bidirectional"))
    )
    (net (code "101") (name "unconnected-(IC_1-PE13-PadP$76)") (class "Default")
      (node (ref "IC_1") (pin "P$76") (pinfunction "PE13_P$76") (pintype "bidirectional"))
    )
    (net (code "102") (name "unconnected-(IC_1-PE14-PadP$77)") (class "Default")
      (node (ref "IC_1") (pin "P$77") (pinfunction "PE14_P$77") (pintype "bidirectional"))
    )
    (net (code "103") (name "unconnected-(IC_1-PE15-PadP$78)") (class "Default")
      (node (ref "IC_1") (pin "P$78") (pinfunction "PE15_P$78") (pintype "bidirectional"))
    )
    (net (code "104") (name "unconnected-(IC_1-PF0-PadP$16)") (class "Default")
      (node (ref "IC_1") (pin "P$16") (pinfunction "PF0_P$16") (pintype "bidirectional"))
    )
    (net (code "105") (name "unconnected-(IC_1-PF1-PadP$17)") (class "Default")
      (node (ref "IC_1") (pin "P$17") (pinfunction "PF1_P$17") (pintype "bidirectional"))
    )
    (net (code "106") (name "unconnected-(IC_1-PF2-PadP$18)") (class "Default")
      (node (ref "IC_1") (pin "P$18") (pinfunction "PF2_P$18") (pintype "bidirectional"))
    )
    (net (code "107") (name "unconnected-(IC_1-PF3-PadP$19)") (class "Default")
      (node (ref "IC_1") (pin "P$19") (pinfunction "PF3_P$19") (pintype "bidirectional"))
    )
    (net (code "108") (name "unconnected-(IC_1-PF4-PadP$20)") (class "Default")
      (node (ref "IC_1") (pin "P$20") (pinfunction "PF4_P$20") (pintype "bidirectional"))
    )
    (net (code "109") (name "unconnected-(IC_1-PF5-PadP$21)") (class "Default")
      (node (ref "IC_1") (pin "P$21") (pinfunction "PF5_P$21") (pintype "bidirectional"))
    )
    (net (code "110") (name "unconnected-(IC_1-PF6-PadP$24)") (class "Default")
      (node (ref "IC_1") (pin "P$24") (pinfunction "PF6_P$24") (pintype "bidirectional"))
    )
    (net (code "111") (name "unconnected-(IC_1-PF7-PadP$25)") (class "Default")
      (node (ref "IC_1") (pin "P$25") (pinfunction "PF7_P$25") (pintype "bidirectional"))
    )
    (net (code "112") (name "unconnected-(IC_1-PF8-PadP$26)") (class "Default")
      (node (ref "IC_1") (pin "P$26") (pinfunction "PF8_P$26") (pintype "bidirectional"))
    )
    (net (code "113") (name "unconnected-(IC_1-PF9-PadP$27)") (class "Default")
      (node (ref "IC_1") (pin "P$27") (pinfunction "PF9_P$27") (pintype "bidirectional"))
    )
    (net (code "114") (name "unconnected-(IC_1-PF10-PadP$28)") (class "Default")
      (node (ref "IC_1") (pin "P$28") (pinfunction "PF10_P$28") (pintype "bidirectional"))
    )
    (net (code "115") (name "unconnected-(IC_1-PF11-PadP$59)") (class "Default")
      (node (ref "IC_1") (pin "P$59") (pinfunction "PF11_P$59") (pintype "bidirectional"))
    )
    (net (code "116") (name "unconnected-(IC_1-PF12-PadP$60)") (class "Default")
      (node (ref "IC_1") (pin "P$60") (pinfunction "PF12_P$60") (pintype "bidirectional"))
    )
    (net (code "117") (name "unconnected-(IC_1-PF13-PadP$63)") (class "Default")
      (node (ref "IC_1") (pin "P$63") (pinfunction "PF13_P$63") (pintype "bidirectional"))
    )
    (net (code "118") (name "unconnected-(IC_1-PF14-PadP$64)") (class "Default")
      (node (ref "IC_1") (pin "P$64") (pinfunction "PF14_P$64") (pintype "bidirectional"))
    )
    (net (code "119") (name "unconnected-(IC_1-PF15-PadP$65)") (class "Default")
      (node (ref "IC_1") (pin "P$65") (pinfunction "PF15_P$65") (pintype "bidirectional"))
    )
    (net (code "120") (name "unconnected-(IC_1-PG0-PadP$66)") (class "Default")
      (node (ref "IC_1") (pin "P$66") (pinfunction "PG0_P$66") (pintype "bidirectional"))
    )
    (net (code "121") (name "unconnected-(IC_1-PG1-PadP$67)") (class "Default")
      (node (ref "IC_1") (pin "P$67") (pinfunction "PG1_P$67") (pintype "bidirectional"))
    )
    (net (code "122") (name "unconnected-(IC_1-PG2-PadP$106)") (class "Default")
      (node (ref "IC_1") (pin "P$106") (pinfunction "PG2_P$106") (pintype "bidirectional"))
    )
    (net (code "123") (name "unconnected-(IC_1-PG3-PadP$107)") (class "Default")
      (node (ref "IC_1") (pin "P$107") (pinfunction "PG3_P$107") (pintype "bidirectional"))
    )
    (net (code "124") (name "unconnected-(IC_1-PG4-PadP$108)") (class "Default")
      (node (ref "IC_1") (pin "P$108") (pinfunction "PG4_P$108") (pintype "bidirectional"))
    )
    (net (code "125") (name "unconnected-(IC_1-PG5-PadP$109)") (class "Default")
      (node (ref "IC_1") (pin "P$109") (pinfunction "PG5_P$109") (pintype "bidirectional"))
    )
    (net (code "126") (name "unconnected-(IC_1-PG6-PadP$110)") (class "Default")
      (node (ref "IC_1") (pin "P$110") (pinfunction "PG6_P$110") (pintype "bidirectional"))
    )
    (net (code "127") (name "unconnected-(IC_1-PG7-PadP$111)") (class "Default")
      (node (ref "IC_1") (pin "P$111") (pinfunction "PG7_P$111") (pintype "bidirectional"))
    )
    (net (code "128") (name "unconnected-(IC_1-PG8-PadP$112)") (class "Default")
      (node (ref "IC_1") (pin "P$112") (pinfunction "PG8_P$112") (pintype "bidirectional"))
    )
    (net (code "129") (name "unconnected-(IC_1-PG9-PadP$152)") (class "Default")
      (node (ref "IC_1") (pin "P$152") (pinfunction "PG9_P$152") (pintype "bidirectional"))
    )
    (net (code "130") (name "unconnected-(IC_1-PG10-PadP$153)") (class "Default")
      (node (ref "IC_1") (pin "P$153") (pinfunction "PG10_P$153") (pintype "bidirectional"))
    )
    (net (code "131") (name "unconnected-(IC_1-PG11-PadP$154)") (class "Default")
      (node (ref "IC_1") (pin "P$154") (pinfunction "PG11_P$154") (pintype "bidirectional"))
    )
    (net (code "132") (name "unconnected-(IC_1-PG12-PadP$155)") (class "Default")
      (node (ref "IC_1") (pin "P$155") (pinfunction "PG12_P$155") (pintype "bidirectional"))
    )
    (net (code "133") (name "unconnected-(IC_1-PG13-PadP$156)") (class "Default")
      (node (ref "IC_1") (pin "P$156") (pinfunction "PG13_P$156") (pintype "bidirectional"))
    )
    (net (code "134") (name "unconnected-(IC_1-PG14-PadP$157)") (class "Default")
      (node (ref "IC_1") (pin "P$157") (pinfunction "PG14_P$157") (pintype "bidirectional"))
    )
    (net (code "135") (name "unconnected-(IC_1-PG15-PadP$160)") (class "Default")
      (node (ref "IC_1") (pin "P$160") (pinfunction "PG15_P$160") (pintype "bidirectional"))
    )
    (net (code "136") (name "unconnected-(IC_1-PH2-PadP$43)") (class "Default")
      (node (ref "IC_1") (pin "P$43") (pinfunction "PH2_P$43") (pintype "bidirectional"))
    )
    (net (code "137") (name "unconnected-(IC_1-PH3-PadP$44)") (class "Default")
      (node (ref "IC_1") (pin "P$44") (pinfunction "PH3_P$44") (pintype "bidirectional"))
    )
    (net (code "138") (name "unconnected-(IC_1-PH4-PadP$45)") (class "Default")
      (node (ref "IC_1") (pin "P$45") (pinfunction "PH4_P$45") (pintype "bidirectional"))
    )
    (net (code "139") (name "unconnected-(IC_1-PH5-PadP$46)") (class "Default")
      (node (ref "IC_1") (pin "P$46") (pinfunction "PH5_P$46") (pintype "bidirectional"))
    )
    (net (code "140") (name "unconnected-(IC_1-PH6-PadP$83)") (class "Default")
      (node (ref "IC_1") (pin "P$83") (pinfunction "PH6_P$83") (pintype "bidirectional"))
    )
    (net (code "141") (name "unconnected-(IC_1-PH7-PadP$84)") (class "Default")
      (node (ref "IC_1") (pin "P$84") (pinfunction "PH7_P$84") (pintype "bidirectional"))
    )
    (net (code "142") (name "unconnected-(IC_1-PH8-PadP$85)") (class "Default")
      (node (ref "IC_1") (pin "P$85") (pinfunction "PH8_P$85") (pintype "bidirectional"))
    )
    (net (code "143") (name "unconnected-(IC_1-PH9-PadP$86)") (class "Default")
      (node (ref "IC_1") (pin "P$86") (pinfunction "PH9_P$86") (pintype "bidirectional"))
    )
    (net (code "144") (name "unconnected-(IC_1-PH10-PadP$87)") (class "Default")
      (node (ref "IC_1") (pin "P$87") (pinfunction "PH10_P$87") (pintype "bidirectional"))
    )
    (net (code "145") (name "unconnected-(IC_1-PH11-PadP$88)") (class "Default")
      (node (ref "IC_1") (pin "P$88") (pinfunction "PH11_P$88") (pintype "bidirectional"))
    )
    (net (code "146") (name "unconnected-(IC_1-PH12-PadP$89)") (class "Default")
      (node (ref "IC_1") (pin "P$89") (pinfunction "PH12_P$89") (pintype "bidirectional"))
    )
    (net (code "147") (name "unconnected-(IC_1-PH13-PadP$128)") (class "Default")
      (node (ref "IC_1") (pin "P$128") (pinfunction "PH13_P$128") (pintype "bidirectional"))
    )
    (net (code "148") (name "unconnected-(IC_1-PH14-PadP$129)") (class "Default")
      (node (ref "IC_1") (pin "P$129") (pinfunction "PH14_P$129") (pintype "bidirectional"))
    )
    (net (code "149") (name "unconnected-(IC_1-PH15-PadP$130)") (class "Default")
      (node (ref "IC_1") (pin "P$130") (pinfunction "PH15_P$130") (pintype "bidirectional"))
    )
    (net (code "150") (name "unconnected-(IC_1-PI0-PadP$131)") (class "Default")
      (node (ref "IC_1") (pin "P$131") (pinfunction "PI0_P$131") (pintype "bidirectional"))
    )
    (net (code "151") (name "unconnected-(IC_1-PI1-PadP$132)") (class "Default")
      (node (ref "IC_1") (pin "P$132") (pinfunction "PI1_P$132") (pintype "bidirectional"))
    )
    (net (code "152") (name "unconnected-(IC_1-PI2-PadP$133)") (class "Default")
      (node (ref "IC_1") (pin "P$133") (pinfunction "PI2_P$133") (pintype "bidirectional"))
    )
    (net (code "153") (name "unconnected-(IC_1-PI3-PadP$134)") (class "Default")
      (node (ref "IC_1") (pin "P$134") (pinfunction "PI3_P$134") (pintype "bidirectional"))
    )
    (net (code "154") (name "unconnected-(IC_1-PI4-PadP$173)") (class "Default")
      (node (ref "IC_1") (pin "P$173") (pinfunction "PI4_P$173") (pintype "bidirectional"))
    )
    (net (code "155") (name "unconnected-(IC_1-PI5-PadP$174)") (class "Default")
      (node (ref "IC_1") (pin "P$174") (pinfunction "PI5_P$174") (pintype "bidirectional"))
    )
    (net (code "156") (name "unconnected-(IC_1-PI6-PadP$175)") (class "Default")
      (node (ref "IC_1") (pin "P$175") (pinfunction "PI6_P$175") (pintype "bidirectional"))
    )
    (net (code "157") (name "unconnected-(IC_1-PI8-PadP$7)") (class "Default")
      (node (ref "IC_1") (pin "P$7") (pinfunction "PI8_P$7") (pintype "bidirectional"))
    )
    (net (code "158") (name "unconnected-(IC_1-PI9-PadP$11)") (class "Default")
      (node (ref "IC_1") (pin "P$11") (pinfunction "PI9_P$11") (pintype "bidirectional"))
    )
    (net (code "159") (name "unconnected-(IC_1-PI10-PadP$12)") (class "Default")
      (node (ref "IC_1") (pin "P$12") (pinfunction "PI10_P$12") (pintype "bidirectional"))
    )
    (net (code "160") (name "unconnected-(IC_1-PI11-PadP$13)") (class "Default")
      (node (ref "IC_1") (pin "P$13") (pinfunction "PI11_P$13") (pintype "bidirectional"))
    )
    (net (code "161") (name "unconnected-(S1-Pad1)") (class "Default")
      (node (ref "S1") (pin "1") (pinfunction "1_1") (pintype "passive"))
    )
    (net (code "162") (name "unconnected-(S1-Pad3)") (class "Default")
      (node (ref "S1") (pin "3") (pinfunction "3_3") (pintype "passive"))
    )
    (net (code "163") (name "unconnected-(S2-Pad1)") (class "Default")
      (node (ref "S2") (pin "1") (pinfunction "1_1") (pintype "passive"))
    )
    (net (code "164") (name "unconnected-(S2-Pad3)") (class "Default")
      (node (ref "S2") (pin "3") (pinfunction "3_3") (pintype "passive"))
    )
    (net (code "165") (name "unconnected-(U$1-CARD_DETECT-PadCD1)") (class "Default")
      (node (ref "U$1") (pin "CD1") (pinfunction "CARD_DETECT_CD1") (pintype "passive"))
    )
    (net (code "166") (name "unconnected-(U$1-CARD_DETECT1-PadCD2)") (class "Default")
      (node (ref "U$1") (pin "CD2") (pinfunction "CARD_DETECT1_CD2") (pintype "passive"))
    )
    (net (code "167") (name "unconnected-(U$1-CS-Pad2)") (class "Default")
      (node (ref "U$1") (pin "2") (pinfunction "CS_2") (pintype "input"))
    )
    (net (code "168") (name "unconnected-(U$1-DAT1-Pad8)") (class "Default")
      (node (ref "U$1") (pin "8") (pinfunction "DAT1_8") (pintype "bidirectional"))
    )
    (net (code "169") (name "unconnected-(U$1-DAT2-Pad1)") (class "Default")
      (node (ref "U$1") (pin "1") (pinfunction "DAT2_1") (pintype "bidirectional"))
    )
    (net (code "170") (name "unconnected-(U$1-DATA_IN-Pad3)") (class "Default")
      (node (ref "U$1") (pin "3") (pinfunction "DATA_IN_3") (pintype "input"))
    )
    (net (code "171") (name "unconnected-(U$1-DATA_OUT-Pad7)") (class "Default")
      (node (ref "U$1") (pin "7") (pinfunction "DATA_OUT_7") (pintype "output"))
    )
    (net (code "172") (name "unconnected-(U$1-SCLK-Pad5)") (class "Default")
      (node (ref "U$1") (pin "5") (pinfunction "SCLK_5") (pintype "input"))
    )
    (net (code "173") (name "unconnected-(WIFI-Pad3)") (class "Default")
      (node (ref "WIFI") (pin "3") (pinfunction "3_3") (pintype "passive"))
    )
    (net (code "174") (name "unconnected-(WIFI-Pad5)") (class "Default")
      (node (ref "WIFI") (pin "5") (pinfunction "5_5") (pintype "passive"))
    )
  )
)
